# OurEDA-P1K_sd.net
KiCad netlist of a schematic drawn in Altium Designer
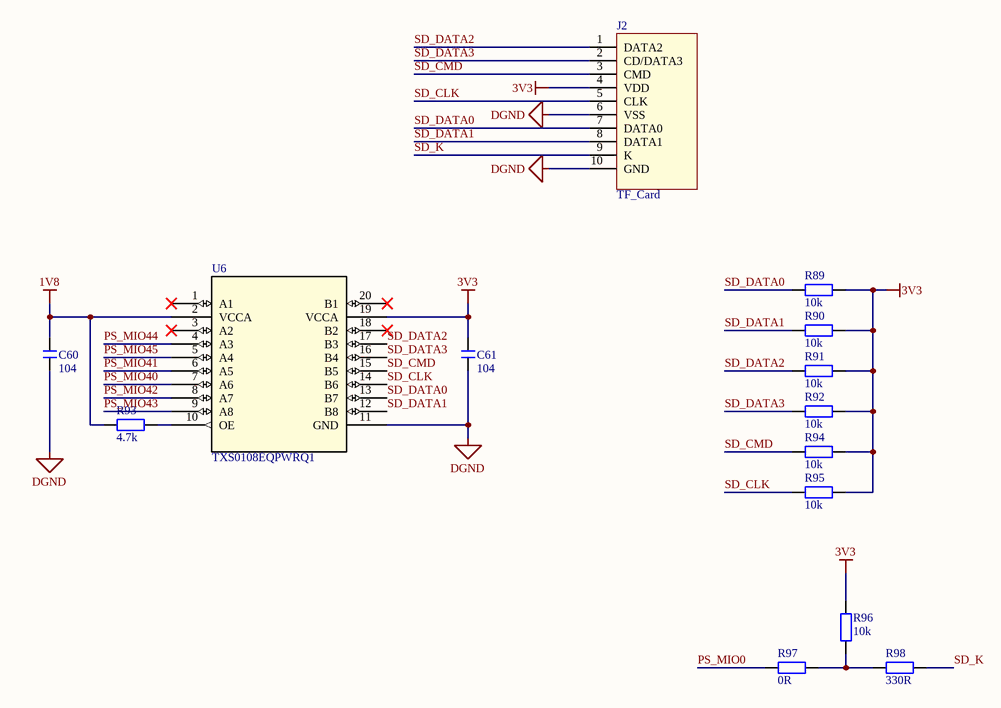
[diagram p0: OurEDA-P1K_sd.SchDoc]

(export (version "E")
  (design (tool "Eeschema 10.0.6"))
  (components
    (comp (ref "C60")
      (value "104")
      (footprint "C 0603_L")
      (description "无极性贴片电容")
      (fields (field (name "版权归属") "源创客"))
      (libsource (lib "3.1   - 电阻-电容-电感") (part "C"))
    )
    (comp (ref "C61")
      (value "104")
      (footprint "C 0603_L")
      (description "无极性贴片电容")
      (fields (field (name "版权归属") "源创客"))
      (libsource (lib "3.1   - 电阻-电容-电感") (part "C"))
    )
    (comp (ref "J2")
      (value "TF_Card")
      (footprint "Micro SD")
      (description "TF卡座")
      (fields (field (name "版权归属") "源创客"))
      (libsource (lib "4.1   - 接口类") (part "TF_Card"))
    )
    (comp (ref "R89")
      (value "10k")
      (footprint "R 0603_L")
      (description "贴片电阻")
      (fields (field (name "版权归属") "源创客"))
      (libsource (lib "3.1   - 电阻-电容-电感") (part "R"))
    )
    (comp (ref "R90")
      (value "10k")
      (footprint "R 0603_L")
      (description "贴片电阻")
      (fields (field (name "版权归属") "源创客"))
      (libsource (lib "3.1   - 电阻-电容-电感") (part "R"))
    )
    (comp (ref "R91")
      (value "10k")
      (footprint "R 0603_L")
      (description "贴片电阻")
      (fields (field (name "版权归属") "源创客"))
      (libsource (lib "3.1   - 电阻-电容-电感") (part "R"))
    )
    (comp (ref "R92")
      (value "10k")
      (footprint "R 0603_L")
      (description "贴片电阻")
      (fields (field (name "版权归属") "源创客"))
      (libsource (lib "3.1   - 电阻-电容-电感") (part "R"))
    )
    (comp (ref "R93")
      (value "4.7k")
      (footprint "R 0603_L")
      (description "贴片电阻")
      (fields (field (name "版权归属") "源创客"))
      (libsource (lib "3.1   - 电阻-电容-电感") (part "R"))
    )
    (comp (ref "R94")
      (value "10k")
      (footprint "R 0603_L")
      (description "贴片电阻")
      (fields (field (name "版权归属") "源创客"))
      (libsource (lib "3.1   - 电阻-电容-电感") (part "R"))
    )
    (comp (ref "R95")
      (value "10k")
      (footprint "R 0603_L")
      (description "贴片电阻")
      (fields (field (name "版权归属") "源创客"))
      (libsource (lib "3.1   - 电阻-电容-电感") (part "R"))
    )
    (comp (ref "R96")
      (value "10k")
      (footprint "R 0603_L")
      (description "贴片电阻")
      (fields (field (name "版权归属") "源创客"))
      (libsource (lib "3.1   - 电阻-电容-电感") (part "R"))
    )
    (comp (ref "R97")
      (value "0R")
      (footprint "R 0603_L")
      (description "贴片电阻")
      (fields (field (name "版权归属") "源创客"))
      (libsource (lib "3.1   - 电阻-电容-电感") (part "R"))
    )
    (comp (ref "R98")
      (value "330R")
      (footprint "R 0603_L")
      (description "贴片电阻")
      (fields (field (name "版权归属") "源创客"))
      (libsource (lib "3.1   - 电阻-电容-电感") (part "R"))
    )
    (comp (ref "U6")
      (value "TXS0108EQPWRQ1")
      (footprint "PW20_TEX")
      (description "No Description Available")
      (fields (field (name "COPYRIGHT") "Copyright (C) 2022 Ultra Librarian. All rights reserved."))
      (libsource (lib "MySchLib") (part "TXS0108EQPWRQ1"))
    )
  )
  (nets
    (net (code "1") (name "/PS_MIO0") (class "Default")
      (node (ref "R97") (pin "2") (pinfunction "2_2") (pintype "passive"))
    )
    (net (code "2") (name "/PS_MIO40") (class "Default")
      (node (ref "U6") (pin "7") (pinfunction "A6_7") (pintype "bidirectional"))
    )
    (net (code "3") (name "/PS_MIO41") (class "Default")
      (node (ref "U6") (pin "6") (pinfunction "A5_6") (pintype "bidirectional"))
    )
    (net (code "4") (name "/PS_MIO42") (class "Default")
      (node (ref "U6") (pin "8") (pinfunction "A7_8") (pintype "bidirectional"))
    )
    (net (code "5") (name "/PS_MIO43") (class "Default")
      (node (ref "U6") (pin "9") (pinfunction "A8_9") (pintype "bidirectional"))
    )
    (net (code "6") (name "/PS_MIO44") (class "Default")
      (node (ref "U6") (pin "4") (pinfunction "A3_4") (pintype "bidirectional"))
    )
    (net (code "7") (name "/PS_MIO45") (class "Default")
      (node (ref "U6") (pin "5") (pinfunction "A4_5") (pintype "bidirectional"))
    )
    (net (code "8") (name "/SD_CLK") (class "Default")
      (node (ref "J2") (pin "5") (pinfunction "CLK_5") (pintype "passive"))
      (node (ref "R95") (pin "2") (pinfunction "2_2") (pintype "passive"))
      (node (ref "U6") (pin "14") (pinfunction "B6_14") (pintype "bidirectional"))
    )
    (net (code "9") (name "/SD_CMD") (class "Default")
      (node (ref "J2") (pin "3") (pinfunction "CMD_3") (pintype "passive"))
      (node (ref "R94") (pin "2") (pinfunction "2_2") (pintype "passive"))
      (node (ref "U6") (pin "15") (pinfunction "B5_15") (pintype "bidirectional"))
    )
    (net (code "10") (name "/SD_DATA0") (class "Default")
      (node (ref "J2") (pin "7") (pinfunction "DATA0_7") (pintype "passive"))
      (node (ref "R89") (pin "2") (pinfunction "2_2") (pintype "passive"))
      (node (ref "U6") (pin "13") (pinfunction "B7_13") (pintype "bidirectional"))
    )
    (net (code "11") (name "/SD_DATA1") (class "Default")
      (node (ref "J2") (pin "8") (pinfunction "DATA1_8") (pintype "passive"))
      (node (ref "R90") (pin "2") (pinfunction "2_2") (pintype "passive"))
      (node (ref "U6") (pin "12") (pinfunction "B8_12") (pintype "bidirectional"))
    )
    (net (code "12") (name "/SD_DATA2") (class "Default")
      (node (ref "J2") (pin "1") (pinfunction "DATA2_1") (pintype "passive"))
      (node (ref "R91") (pin "2") (pinfunction "2_2") (pintype "passive"))
      (node (ref "U6") (pin "17") (pinfunction "B3_17") (pintype "bidirectional"))
    )
    (net (code "13") (name "/SD_DATA3") (class "Default")
      (node (ref "J2") (pin "2") (pinfunction "CD/DATA3_2") (pintype "passive"))
      (node (ref "R92") (pin "2") (pinfunction "2_2") (pintype "passive"))
      (node (ref "U6") (pin "16") (pinfunction "B4_16") (pintype "bidirectional"))
    )
    (net (code "14") (name "/SD_K") (class "Default")
      (node (ref "J2") (pin "9") (pinfunction "K_9") (pintype "passive"))
      (node (ref "R98") (pin "1") (pinfunction "1_1") (pintype "passive"))
    )
    (net (code "15") (name "1V8") (class "Default")
      (node (ref "C60") (pin "1") (pinfunction "1_1") (pintype "passive"))
      (node (ref "R93") (pin "2") (pinfunction "2_2") (pintype "passive"))
      (node (ref "U6") (pin "2") (pinfunction "VCCA_2") (pintype "power_in"))
    )
    (net (code "16") (name "3V3") (class "Default")
      (node (ref "C61") (pin "1") (pinfunction "1_1") (pintype "passive"))
      (node (ref "J2") (pin "4") (pinfunction "VDD_4") (pintype "passive"))
      (node (ref "R89") (pin "1") (pinfunction "1_1") (pintype "passive"))
      (node (ref "R90") (pin "1") (pinfunction "1_1") (pintype "passive"))
      (node (ref "R91") (pin "1") (pinfunction "1_1") (pintype "passive"))
      (node (ref "R92") (pin "1") (pinfunction "1_1") (pintype "passive"))
      (node (ref "R94") (pin "1") (pinfunction "1_1") (pintype "passive"))
      (node (ref "R95") (pin "1") (pinfunction "1_1") (pintype "passive"))
      (node (ref "R96") (pin "2") (pinfunction "2_2") (pintype "passive"))
      (node (ref "U6") (pin "19") (pinfunction "VCCA_19") (pintype "power_in"))
    )
    (net (code "17") (name "DGND") (class "Default")
      (node (ref "C60") (pin "2") (pinfunction "2_2") (pintype "passive"))
      (node (ref "C61") (pin "2") (pinfunction "2_2") (pintype "passive"))
      (node (ref "J2") (pin "10") (pinfunction "GND_10") (pintype "passive"))
      (node (ref "J2") (pin "6") (pinfunction "VSS_6") (pintype "passive"))
      (node (ref "U6") (pin "11") (pinfunction "GND_11") (pintype "power_in"))
    )
    (net (code "18") (name "Net-(R96-Pad1)") (class "Default")
      (node (ref "R96") (pin "1") (pinfunction "1_1") (pintype "passive"))
      (node (ref "R97") (pin "1") (pinfunction "1_1") (pintype "passive"))
      (node (ref "R98") (pin "2") (pinfunction "2_2") (pintype "passive"))
    )
    (net (code "19") (name "Net-(U6-OE)") (class "Default")
      (node (ref "R93") (pin "1") (pinfunction "1_1") (pintype "passive"))
      (node (ref "U6") (pin "10") (pinfunction "OE_10") (pintype "output"))
    )
    (net (code "20") (name "unconnected-(U6-A1-Pad1)") (class "Default")
      (node (ref "U6") (pin "1") (pinfunction "A1_1") (pintype "bidirectional+no_connect"))
    )
    (net (code "21") (name "unconnected-(U6-A2-Pad3)") (class "Default")
      (node (ref "U6") (pin "3") (pinfunction "A2_3") (pintype "bidirectional+no_connect"))
    )
    (net (code "22") (name "unconnected-(U6-B1-Pad20)") (class "Default")
      (node (ref "U6") (pin "20") (pinfunction "B1_20") (pintype "bidirectional+no_connect"))
    )
    (net (code "23") (name "unconnected-(U6-B2-Pad18)") (class "Default")
      (node (ref "U6") (pin "18") (pinfunction "B2_18") (pintype "bidirectional+no_connect"))
    )
  )
)
